# working.net
KiCad netlist of a schematic drawn in EAGLE
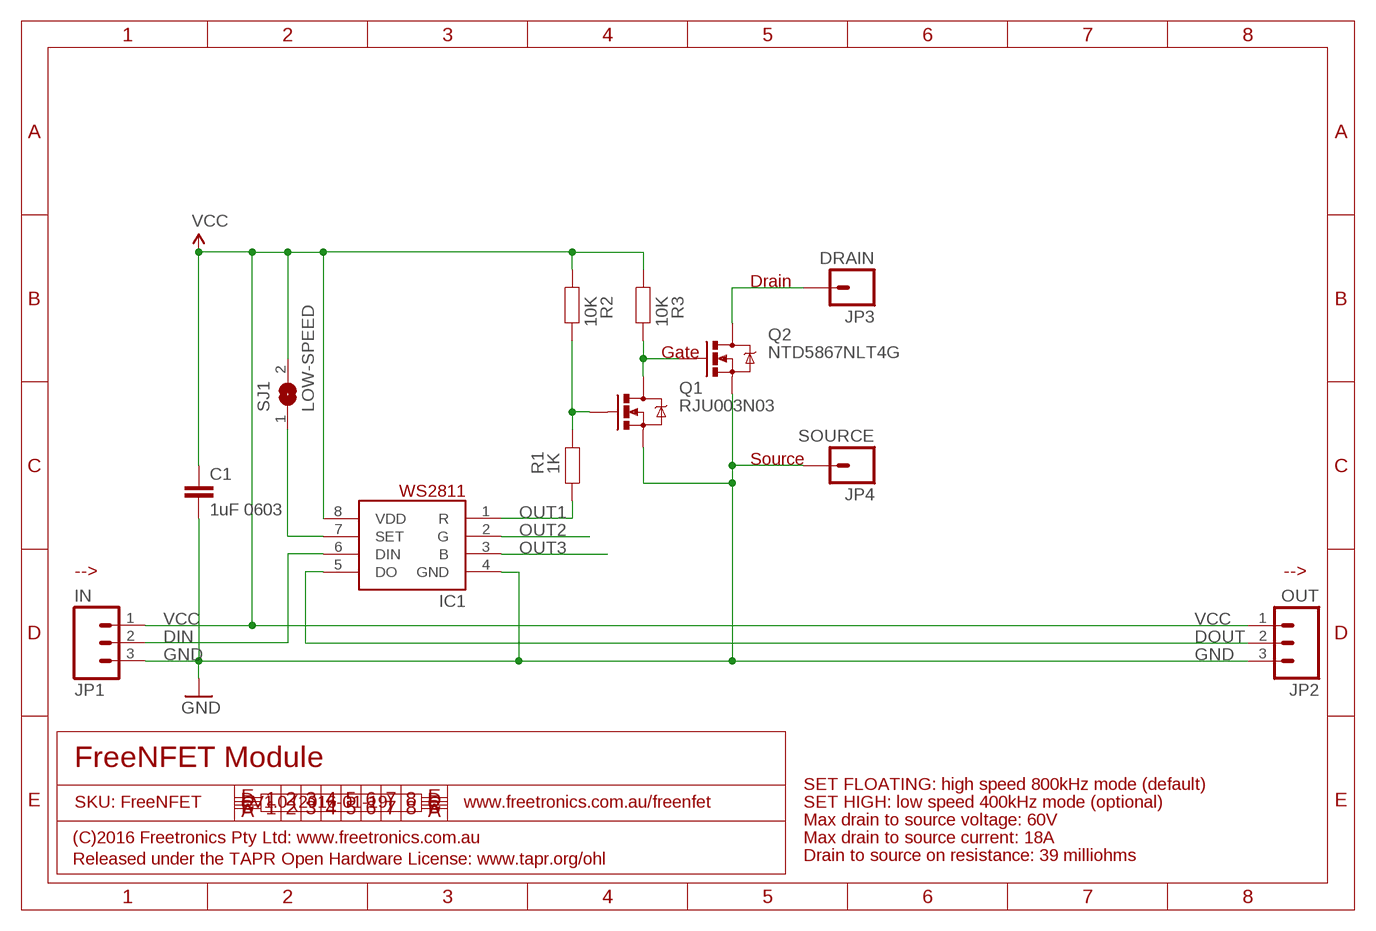
[diagram p0: schematic, sheet 1]

(export (version "E")
  (design (tool "Eeschema 10.0.6"))
  (components
    (comp (ref "C1")
      (value "1uF 0603")
      (footprint "eagle-import:0603")
      (libsource (lib "eagle-import") (part "CAP0603"))
    )
    (comp (ref "IC1")
      (value "WS2811-SOP8")
      (footprint "eagle-import:SO08-SKINNYPADS")
      (libsource (lib "eagle-import") (part "WS2811-SOP8"))
    )
    (comp (ref "JP1")
      (value "IN")
      (footprint "eagle-import:1X03")
      (libsource (lib "eagle-import") (part "M03PTH"))
    )
    (comp (ref "JP2")
      (value "OUT")
      (footprint "eagle-import:1X03")
      (libsource (lib "eagle-import") (part "M03PTH"))
    )
    (comp (ref "JP3")
      (value "DRAIN")
      (footprint "eagle-import:1X01LARGE")
      (libsource (lib "eagle-import") (part "M01PTH_LARGE"))
    )
    (comp (ref "JP4")
      (value "SOURCE")
      (footprint "eagle-import:1X01LARGE")
      (libsource (lib "eagle-import") (part "M01PTH_LARGE"))
    )
    (comp (ref "Q1")
      (value "RJU003N03")
      (footprint "eagle-import:SOT32-3")
      (libsource (lib "eagle-import") (part "MOSFET-NSOT-323"))
    )
    (comp (ref "Q2")
      (value "NTD5867NLT4G")
      (footprint "eagle-import:DPACK")
      (libsource (lib "eagle-import") (part "MOSFET-NCHANNELDPAK"))
    )
    (comp (ref "R1")
      (value "1K")
      (footprint "eagle-import:0603")
      (libsource (lib "eagle-import") (part "RESISTOR0603"))
    )
    (comp (ref "R2")
      (value "10K")
      (footprint "eagle-import:0603")
      (libsource (lib "eagle-import") (part "RESISTOR0603"))
    )
    (comp (ref "R3")
      (value "10K")
      (footprint "eagle-import:0603")
      (libsource (lib "eagle-import") (part "RESISTOR0603"))
    )
    (comp (ref "SJ1")
      (value "LOW-SPEED")
      (footprint "eagle-import:SJ")
      (libsource (lib "eagle-import") (part "SJN"))
    )
  )
  (nets
    (net (code "1") (name "/DIN") (class "Default")
      (node (ref "IC1") (pin "6") (pinfunction "DIN_6") (pintype "input"))
      (node (ref "JP1") (pin "2") (pinfunction "2_2") (pintype "passive"))
    )
    (net (code "2") (name "/DOUT") (class "Default")
      (node (ref "IC1") (pin "5") (pinfunction "DO_5") (pintype "output"))
      (node (ref "JP2") (pin "2") (pinfunction "2_2") (pintype "passive"))
    )
    (net (code "3") (name "/OUT1") (class "Default")
      (node (ref "IC1") (pin "1") (pinfunction "R_1") (pintype "open_collector"))
      (node (ref "R1") (pin "2") (pinfunction "2_2") (pintype "passive"))
    )
    (net (code "4") (name "/OUT2") (class "Default")
      (node (ref "IC1") (pin "2") (pinfunction "G_2") (pintype "open_collector"))
    )
    (net (code "5") (name "/OUT3") (class "Default")
      (node (ref "IC1") (pin "3") (pinfunction "B_3") (pintype "open_collector"))
    )
    (net (code "6") (name "GND") (class "Default")
      (node (ref "C1") (pin "2") (pinfunction "2_2") (pintype "passive"))
      (node (ref "IC1") (pin "4") (pinfunction "GND_4") (pintype "power_in"))
      (node (ref "JP1") (pin "3") (pinfunction "3_3") (pintype "passive"))
      (node (ref "JP2") (pin "3") (pinfunction "3_3") (pintype "passive"))
      (node (ref "JP4") (pin "1") (pinfunction "1_1") (pintype "passive"))
      (node (ref "Q1") (pin "2") (pinfunction "S_2") (pintype "passive"))
      (node (ref "Q2") (pin "3") (pinfunction "S_3") (pintype "passive"))
    )
    (net (code "7") (name "Net-(IC1-SET)") (class "Default")
      (node (ref "IC1") (pin "7") (pinfunction "SET_7") (pintype "input"))
      (node (ref "SJ1") (pin "1") (pinfunction "1_1") (pintype "passive"))
    )
    (net (code "8") (name "Net-(Q1-D)") (class "Default")
      (node (ref "Q1") (pin "3") (pinfunction "D_3") (pintype "passive"))
      (node (ref "Q2") (pin "1") (pinfunction "G_1") (pintype "passive"))
      (node (ref "R3") (pin "1") (pinfunction "1_1") (pintype "passive"))
    )
    (net (code "9") (name "Net-(Q1-G)") (class "Default")
      (node (ref "Q1") (pin "1") (pinfunction "G_1") (pintype "passive"))
      (node (ref "R1") (pin "1") (pinfunction "1_1") (pintype "passive"))
      (node (ref "R2") (pin "1") (pinfunction "1_1") (pintype "passive"))
    )
    (net (code "10") (name "Net-(Q2-D)") (class "Default")
      (node (ref "JP3") (pin "1") (pinfunction "1_1") (pintype "passive"))
      (node (ref "Q2") (pin "2") (pinfunction "D_2") (pintype "passive"))
    )
    (net (code "11") (name "VCC") (class "Default")
      (node (ref "C1") (pin "1") (pinfunction "1_1") (pintype "passive"))
      (node (ref "IC1") (pin "8") (pinfunction "VDD_8") (pintype "power_in"))
      (node (ref "JP1") (pin "1") (pinfunction "1_1") (pintype "passive"))
      (node (ref "JP2") (pin "1") (pinfunction "1_1") (pintype "passive"))
      (node (ref "R2") (pin "2") (pinfunction "2_2") (pintype "passive"))
      (node (ref "R3") (pin "2") (pinfunction "2_2") (pintype "passive"))
      (node (ref "SJ1") (pin "2") (pinfunction "2_2") (pintype "passive"))
    )
  )
)
